# RP2350.net
KiCad netlist of a schematic drawn in Altium Designer
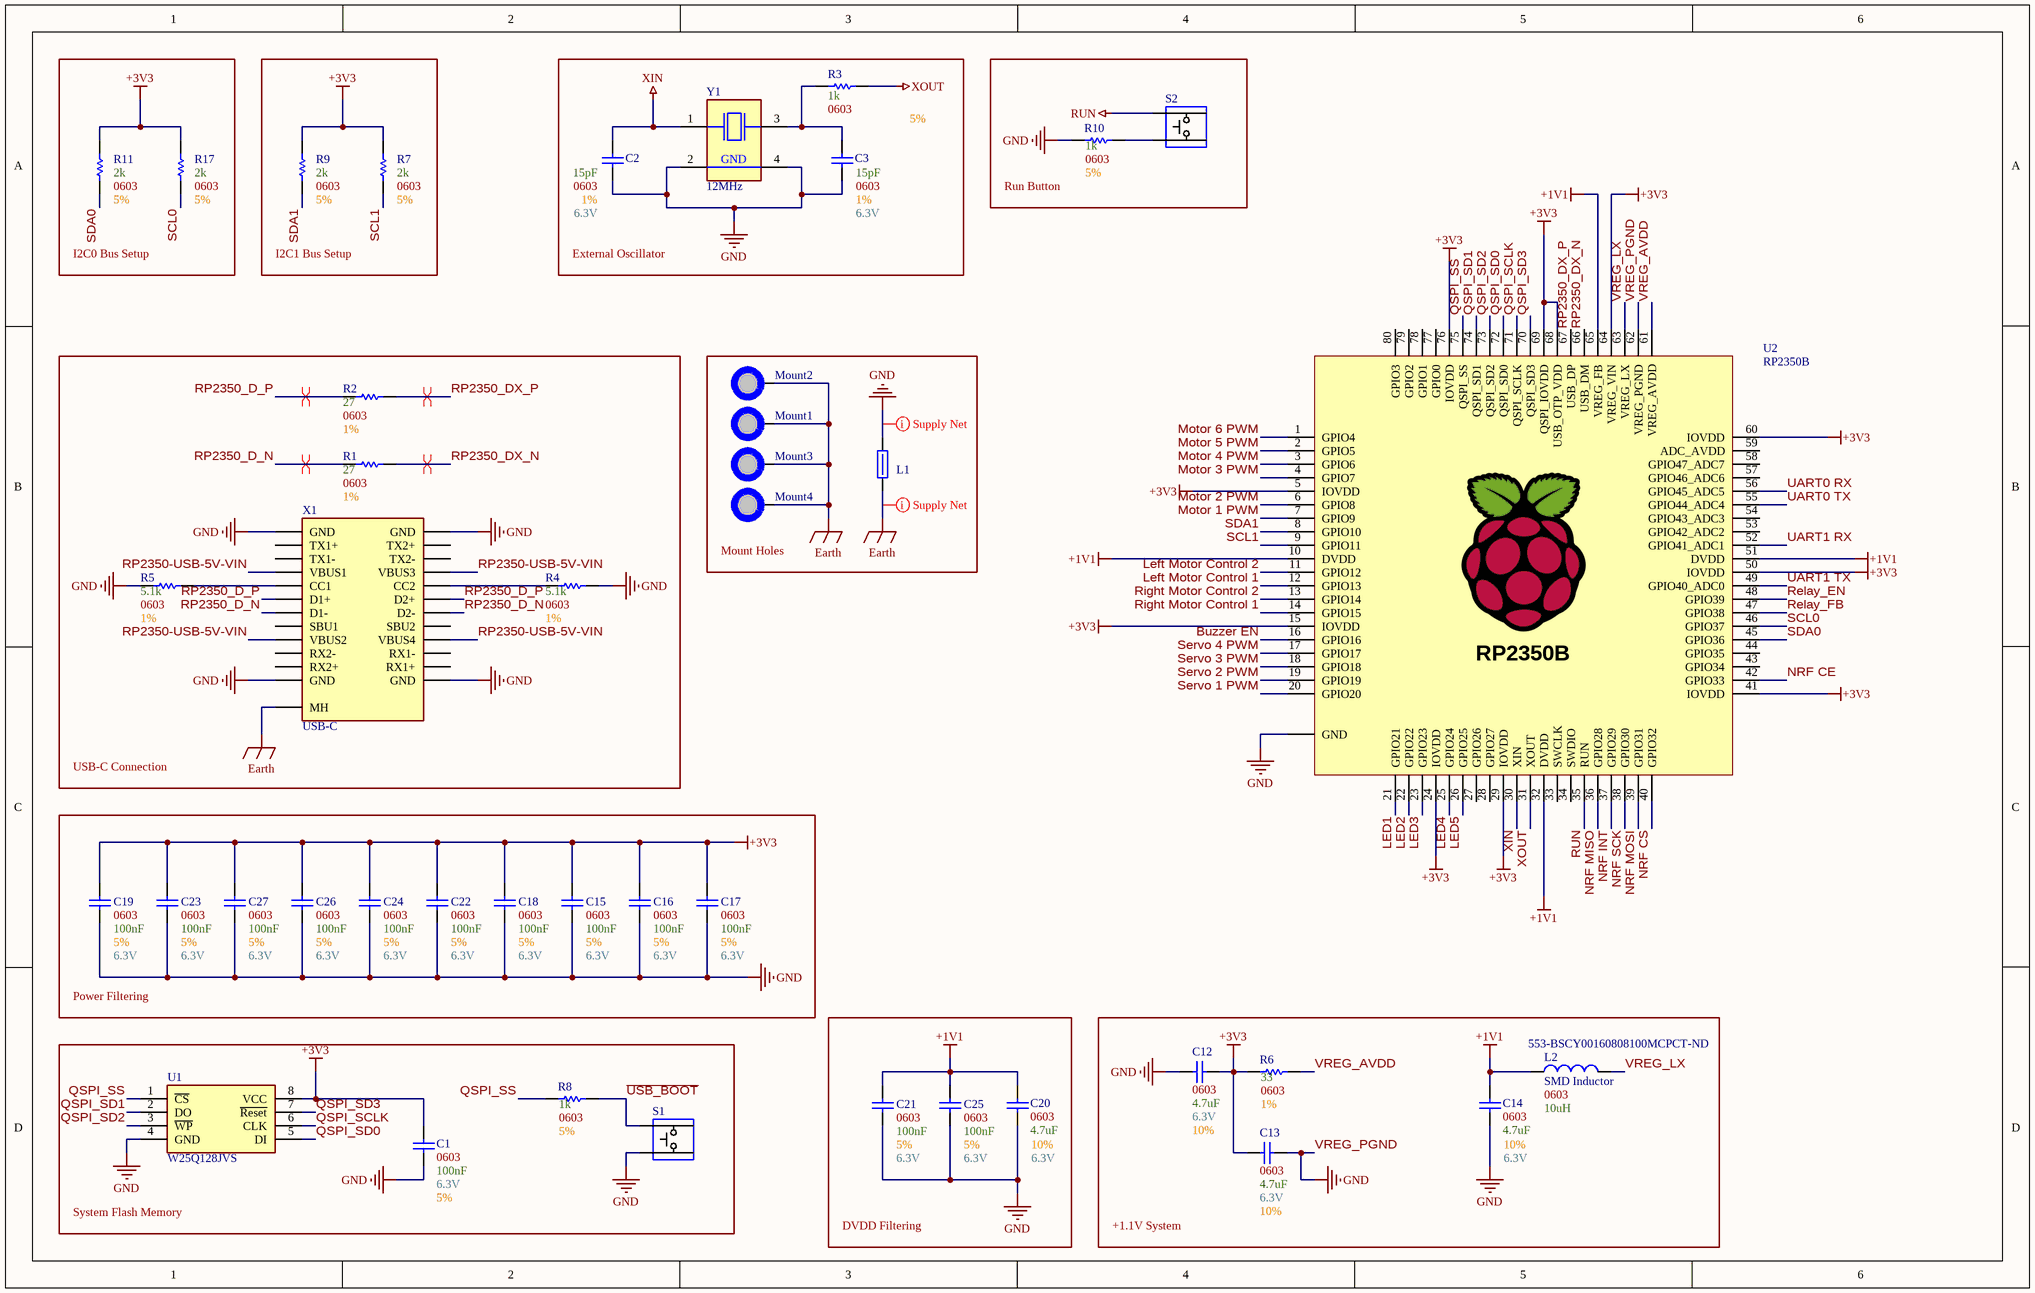
[diagram p0: RP2350.SchDoc]

(export (version "E")
  (design (tool "Eeschema 10.0.6"))
  (components
    (comp (ref "C1")
      (value "[Cap] SMD Nonpolarized")
      (footprint "[Cap] SMD 0603")
      (fields
        (field (name "SIZE PACKAGE") "0603")
        (field (name "CAPACITANCE") "100nF")
        (field (name "VOLTAGE") "6.3V")
        (field (name "TOLERANCE") "5%")
      )
      (libsource (lib "RADM Components") (part "[Cap] SMD Nonpolarized"))
    )
    (comp (ref "C2")
      (value "[Cap] SMD Nonpolarized")
      (footprint "[Cap] SMD 0603")
      (fields
        (field (name "SIZE PACKAGE") "0603")
        (field (name "CAPACITANCE") "15pF")
        (field (name "VOLTAGE") "6.3V")
        (field (name "TOLERANCE") "1%")
      )
      (libsource (lib "RADM Components") (part "[Cap] SMD Nonpolarized"))
    )
    (comp (ref "C3")
      (value "[Cap] SMD Nonpolarized")
      (footprint "[Cap] SMD 0603")
      (fields
        (field (name "SIZE PACKAGE") "0603")
        (field (name "CAPACITANCE") "15pF")
        (field (name "VOLTAGE") "6.3V")
        (field (name "TOLERANCE") "1%")
      )
      (libsource (lib "RADM Components") (part "[Cap] SMD Nonpolarized"))
    )
    (comp (ref "C12")
      (value "[Cap] SMD Nonpolarized")
      (footprint "[Cap] SMD 0603")
      (fields
        (field (name "SIZE PACKAGE") "0603")
        (field (name "CAPACITANCE") "4.7uF")
        (field (name "VOLTAGE") "6.3V")
        (field (name "TOLERANCE") "10%")
      )
      (libsource (lib "RADM Components") (part "[Cap] SMD Nonpolarized"))
    )
    (comp (ref "C13")
      (value "[Cap] SMD Nonpolarized")
      (footprint "[Cap] SMD 0603")
      (fields
        (field (name "SIZE PACKAGE") "0603")
        (field (name "CAPACITANCE") "4.7uF")
        (field (name "VOLTAGE") "6.3V")
        (field (name "TOLERANCE") "10%")
      )
      (libsource (lib "RADM Components") (part "[Cap] SMD Nonpolarized"))
    )
    (comp (ref "C14")
      (value "[Cap] SMD Nonpolarized")
      (footprint "[Cap] SMD 0603")
      (fields
        (field (name "SIZE PACKAGE") "0603")
        (field (name "CAPACITANCE") "4.7uF")
        (field (name "VOLTAGE") "6.3V")
        (field (name "TOLERANCE") "10%")
      )
      (libsource (lib "RADM Components") (part "[Cap] SMD Nonpolarized"))
    )
    (comp (ref "C15")
      (value "[Cap] SMD Nonpolarized")
      (footprint "[Cap] SMD 0603")
      (fields
        (field (name "SIZE PACKAGE") "0603")
        (field (name "CAPACITANCE") "100nF")
        (field (name "VOLTAGE") "6.3V")
        (field (name "TOLERANCE") "5%")
      )
      (libsource (lib "RADM Components") (part "[Cap] SMD Nonpolarized"))
    )
    (comp (ref "C16")
      (value "[Cap] SMD Nonpolarized")
      (footprint "[Cap] SMD 0603")
      (fields
        (field (name "SIZE PACKAGE") "0603")
        (field (name "CAPACITANCE") "100nF")
        (field (name "VOLTAGE") "6.3V")
        (field (name "TOLERANCE") "5%")
      )
      (libsource (lib "RADM Components") (part "[Cap] SMD Nonpolarized"))
    )
    (comp (ref "C17")
      (value "[Cap] SMD Nonpolarized")
      (footprint "[Cap] SMD 0603")
      (fields
        (field (name "SIZE PACKAGE") "0603")
        (field (name "CAPACITANCE") "100nF")
        (field (name "VOLTAGE") "6.3V")
        (field (name "TOLERANCE") "5%")
      )
      (libsource (lib "RADM Components") (part "[Cap] SMD Nonpolarized"))
    )
    (comp (ref "C18")
      (value "[Cap] SMD Nonpolarized")
      (footprint "[Cap] SMD 0603")
      (fields
        (field (name "SIZE PACKAGE") "0603")
        (field (name "CAPACITANCE") "100nF")
        (field (name "VOLTAGE") "6.3V")
        (field (name "TOLERANCE") "5%")
      )
      (libsource (lib "RADM Components") (part "[Cap] SMD Nonpolarized"))
    )
    (comp (ref "C19")
      (value "[Cap] SMD Nonpolarized")
      (footprint "[Cap] SMD 0603")
      (fields
        (field (name "SIZE PACKAGE") "0603")
        (field (name "CAPACITANCE") "100nF")
        (field (name "VOLTAGE") "6.3V")
        (field (name "TOLERANCE") "5%")
      )
      (libsource (lib "RADM Components") (part "[Cap] SMD Nonpolarized"))
    )
    (comp (ref "C20")
      (value "[Cap] SMD Nonpolarized")
      (footprint "[Cap] SMD 0603")
      (fields
        (field (name "SIZE PACKAGE") "0603")
        (field (name "CAPACITANCE") "4.7uF")
        (field (name "VOLTAGE") "6.3V")
        (field (name "TOLERANCE") "10%")
      )
      (libsource (lib "RADM Components") (part "[Cap] SMD Nonpolarized"))
    )
    (comp (ref "C21")
      (value "[Cap] SMD Nonpolarized")
      (footprint "[Cap] SMD 0603")
      (fields
        (field (name "SIZE PACKAGE") "0603")
        (field (name "CAPACITANCE") "100nF")
        (field (name "VOLTAGE") "6.3V")
        (field (name "TOLERANCE") "5%")
      )
      (libsource (lib "RADM Components") (part "[Cap] SMD Nonpolarized"))
    )
    (comp (ref "C22")
      (value "[Cap] SMD Nonpolarized")
      (footprint "[Cap] SMD 0603")
      (fields
        (field (name "SIZE PACKAGE") "0603")
        (field (name "CAPACITANCE") "100nF")
        (field (name "VOLTAGE") "6.3V")
        (field (name "TOLERANCE") "5%")
      )
      (libsource (lib "RADM Components") (part "[Cap] SMD Nonpolarized"))
    )
    (comp (ref "C23")
      (value "[Cap] SMD Nonpolarized")
      (footprint "[Cap] SMD 0603")
      (fields
        (field (name "SIZE PACKAGE") "0603")
        (field (name "CAPACITANCE") "100nF")
        (field (name "VOLTAGE") "6.3V")
        (field (name "TOLERANCE") "5%")
      )
      (libsource (lib "RADM Components") (part "[Cap] SMD Nonpolarized"))
    )
    (comp (ref "C24")
      (value "[Cap] SMD Nonpolarized")
      (footprint "[Cap] SMD 0603")
      (fields
        (field (name "SIZE PACKAGE") "0603")
        (field (name "CAPACITANCE") "100nF")
        (field (name "VOLTAGE") "6.3V")
        (field (name "TOLERANCE") "5%")
      )
      (libsource (lib "RADM Components") (part "[Cap] SMD Nonpolarized"))
    )
    (comp (ref "C25")
      (value "[Cap] SMD Nonpolarized")
      (footprint "[Cap] SMD 0603")
      (fields
        (field (name "SIZE PACKAGE") "0603")
        (field (name "CAPACITANCE") "100nF")
        (field (name "VOLTAGE") "6.3V")
        (field (name "TOLERANCE") "5%")
      )
      (libsource (lib "RADM Components") (part "[Cap] SMD Nonpolarized"))
    )
    (comp (ref "C26")
      (value "[Cap] SMD Nonpolarized")
      (footprint "[Cap] SMD 0603")
      (fields
        (field (name "SIZE PACKAGE") "0603")
        (field (name "CAPACITANCE") "100nF")
        (field (name "VOLTAGE") "6.3V")
        (field (name "TOLERANCE") "5%")
      )
      (libsource (lib "RADM Components") (part "[Cap] SMD Nonpolarized"))
    )
    (comp (ref "C27")
      (value "[Cap] SMD Nonpolarized")
      (footprint "[Cap] SMD 0603")
      (fields
        (field (name "SIZE PACKAGE") "0603")
        (field (name "CAPACITANCE") "100nF")
        (field (name "VOLTAGE") "6.3V")
        (field (name "TOLERANCE") "5%")
      )
      (libsource (lib "RADM Components") (part "[Cap] SMD Nonpolarized"))
    )
    (comp (ref "L1")
      (value "652-MH2029-300Y")
      (footprint "[Ferrite] SMD Bead 0805 (1)")
      (libsource (lib "RADM Components") (part "[Ferrite] SMD Ferrite Bead (1)"))
    )
    (comp (ref "L2")
      (value "SMD Inductor")
      (footprint "[Inductor] SMD 0603")
      (fields
        (field (name "SIZE PACKAGE") "0603")
        (field (name "INDUCTANCE") "10uH")
        (field (name "SUPPLIER PART NUMBER 1") "553-BSCY00160808100MCPCT-ND")
      )
      (libsource (lib "RADM Components") (part "[Inductor] SMD Inductor"))
    )
    (comp (ref "Mount1")
      (value "M3 Mount Hole")
      (footprint "[Mount] M3 Mount Hole")
      (description "Place at least 4.5mm from board edge. Plated.")
      (libsource (lib "RADM Connectors") (part "[Mount] M3 Mount Hole"))
    )
    (comp (ref "Mount2")
      (value "M3 Mount Hole")
      (footprint "[Mount] M3 Mount Hole")
      (description "Place at least 4.5mm from board edge. Plated.")
      (libsource (lib "RADM Connectors") (part "[Mount] M3 Mount Hole"))
    )
    (comp (ref "Mount3")
      (value "M3 Mount Hole")
      (footprint "[Mount] M3 Mount Hole")
      (description "Place at least 4.5mm from board edge. Plated.")
      (libsource (lib "RADM Connectors") (part "[Mount] M3 Mount Hole"))
    )
    (comp (ref "Mount4")
      (value "M3 Mount Hole")
      (footprint "[Mount] M3 Mount Hole")
      (description "Place at least 4.5mm from board edge. Plated.")
      (libsource (lib "RADM Connectors") (part "[Mount] M3 Mount Hole"))
    )
    (comp (ref "R1")
      (value "[Res] SMD Resistor")
      (footprint "[Res] SMD 0603")
      (description "Generic")
      (fields
        (field (name "TOLERANCE") "1%")
        (field (name "RESISTANCE") "27")
        (field (name "SIZE PACKAGE") "0603")
      )
      (libsource (lib "RADM Components") (part "[Res] SMD Resistor"))
    )
    (comp (ref "R2")
      (value "[Res] SMD Resistor")
      (footprint "[Res] SMD 0603")
      (description "Generic")
      (fields
        (field (name "TOLERANCE") "1%")
        (field (name "RESISTANCE") "27")
        (field (name "SIZE PACKAGE") "0603")
      )
      (libsource (lib "RADM Components") (part "[Res] SMD Resistor"))
    )
    (comp (ref "R3")
      (value "[Res] SMD Resistor")
      (footprint "[Res] SMD 0603")
      (description "Generic")
      (fields
        (field (name "RESISTANCE") "1k")
        (field (name "SIZE PACKAGE") "0603")
        (field (name "TOLERANCE") "5%")
      )
      (libsource (lib "RADM Components") (part "[Res] SMD Resistor"))
    )
    (comp (ref "R4")
      (value "[Res] SMD Resistor")
      (footprint "[Res] SMD 0603")
      (description "Generic")
      (fields
        (field (name "TOLERANCE") "1%")
        (field (name "RESISTANCE") "5.1k")
        (field (name "SIZE PACKAGE") "0603")
      )
      (libsource (lib "RADM Components") (part "[Res] SMD Resistor"))
    )
    (comp (ref "R5")
      (value "[Res] SMD Resistor")
      (footprint "[Res] SMD 0603")
      (description "Generic")
      (fields
        (field (name "TOLERANCE") "1%")
        (field (name "RESISTANCE") "5.1k")
        (field (name "SIZE PACKAGE") "0603")
      )
      (libsource (lib "RADM Components") (part "[Res] SMD Resistor"))
    )
    (comp (ref "R6")
      (value "[Res] SMD Resistor")
      (footprint "[Res] SMD 0603")
      (description "Generic")
      (fields
        (field (name "RESISTANCE") "33")
        (field (name "SIZE PACKAGE") "0603")
        (field (name "TOLERANCE") "1%")
      )
      (libsource (lib "RADM Components") (part "[Res] SMD Resistor"))
    )
    (comp (ref "R7")
      (value "[Res] SMD Resistor")
      (footprint "[Res] SMD 0603")
      (description "Generic")
      (fields
        (field (name "RESISTANCE") "2k")
        (field (name "SIZE PACKAGE") "0603")
        (field (name "TOLERANCE") "5%")
      )
      (libsource (lib "RADM Components") (part "[Res] SMD Resistor"))
    )
    (comp (ref "R8")
      (value "[Res] SMD Resistor")
      (footprint "[Res] SMD 0603")
      (description "Generic")
      (fields
        (field (name "RESISTANCE") "1k")
        (field (name "SIZE PACKAGE") "0603")
        (field (name "TOLERANCE") "5%")
      )
      (libsource (lib "RADM Components") (part "[Res] SMD Resistor"))
    )
    (comp (ref "R9")
      (value "[Res] SMD Resistor")
      (footprint "[Res] SMD 0603")
      (description "Generic")
      (fields
        (field (name "RESISTANCE") "2k")
        (field (name "SIZE PACKAGE") "0603")
        (field (name "TOLERANCE") "5%")
      )
      (libsource (lib "RADM Components") (part "[Res] SMD Resistor"))
    )
    (comp (ref "R10")
      (value "[Res] SMD Resistor")
      (footprint "[Res] SMD 0603")
      (description "Generic")
      (fields
        (field (name "RESISTANCE") "1k")
        (field (name "SIZE PACKAGE") "0603")
        (field (name "TOLERANCE") "5%")
      )
      (libsource (lib "RADM Components") (part "[Res] SMD Resistor"))
    )
    (comp (ref "R11")
      (value "[Res] SMD Resistor")
      (footprint "[Res] SMD 0603")
      (description "Generic")
      (fields
        (field (name "RESISTANCE") "2k")
        (field (name "SIZE PACKAGE") "0603")
        (field (name "TOLERANCE") "5%")
      )
      (libsource (lib "RADM Components") (part "[Res] SMD Resistor"))
    )
    (comp (ref "R17")
      (value "[Res] SMD Resistor")
      (footprint "[Res] SMD 0603")
      (description "Generic")
      (fields
        (field (name "RESISTANCE") "2k")
        (field (name "SIZE PACKAGE") "0603")
        (field (name "TOLERANCE") "5%")
      )
      (libsource (lib "RADM Components") (part "[Res] SMD Resistor"))
    )
    (comp (ref "S1")
      (value "Standard pushbutton")
      (footprint "[Switch] Pushbutton")
      (libsource (lib "RADM Components") (part "[Switch] Pushbutton"))
    )
    (comp (ref "S2")
      (value "Standard pushbutton")
      (footprint "[Switch] Pushbutton")
      (libsource (lib "RADM Components") (part "[Switch] Pushbutton"))
    )
    (comp (ref "U1")
      (value "W25Q128JVS")
      (footprint "[Mem] 16Mb Flash Memory")
      (description "W25Q128JVSIQ TR")
      (libsource (lib "RADM Components") (part "[Mem] 16Mb Flash Memory"))
    )
    (comp (ref "U2")
      (value "RP2350B")
      (footprint "[MCU] RP2350B")
      (description "QFN-80 Package")
      (libsource (lib "RADM Components") (part "[MCU] RP2350B"))
    )
    (comp (ref "X1")
      (value "USB-C")
      (footprint "[Port] USB-C")
      (libsource (lib "RADM Connectors") (part "[Port] USB Type-C"))
    )
    (comp (ref "Y1")
      (value "12MHz")
      (footprint "[XTAL] SMD 12MHz")
      (description "815-ABM8-272-T3")
      (libsource (lib "RADM Components") (part "[XTAL] SMD 12MHz"))
    )
  )
  (nets
    (net (code "1") (name "+1V1") (class "Default")
      (node (ref "C14") (pin "2") (pinfunction "2_2") (pintype "passive"))
      (node (ref "C20") (pin "2") (pinfunction "2_2") (pintype "passive"))
      (node (ref "C21") (pin "2") (pinfunction "2_2") (pintype "passive"))
      (node (ref "C25") (pin "2") (pinfunction "2_2") (pintype "passive"))
      (node (ref "L2") (pin "1") (pinfunction "1_1") (pintype "passive"))
      (node (ref "U2") (pin "10") (pinfunction "DVDD_10") (pintype "passive"))
      (node (ref "U2") (pin "32") (pinfunction "DVDD_32") (pintype "passive"))
      (node (ref "U2") (pin "51") (pinfunction "DVDD_51") (pintype "passive"))
      (node (ref "U2") (pin "65") (pinfunction "VREG_FB_65") (pintype "passive"))
    )
    (net (code "2") (name "+3V3") (class "Default")
      (node (ref "C1") (pin "1") (pinfunction "1_1") (pintype "passive"))
      (node (ref "C12") (pin "1") (pinfunction "1_1") (pintype "passive"))
      (node (ref "C13") (pin "2") (pinfunction "2_2") (pintype "passive"))
      (node (ref "C15") (pin "2") (pinfunction "2_2") (pintype "passive"))
      (node (ref "C16") (pin "2") (pinfunction "2_2") (pintype "passive"))
      (node (ref "C17") (pin "2") (pinfunction "2_2") (pintype "passive"))
      (node (ref "C18") (pin "2") (pinfunction "2_2") (pintype "passive"))
      (node (ref "C19") (pin "2") (pinfunction "2_2") (pintype "passive"))
      (node (ref "C22") (pin "2") (pinfunction "2_2") (pintype "passive"))
      (node (ref "C23") (pin "2") (pinfunction "2_2") (pintype "passive"))
      (node (ref "C24") (pin "2") (pinfunction "2_2") (pintype "passive"))
      (node (ref "C26") (pin "2") (pinfunction "2_2") (pintype "passive"))
      (node (ref "C27") (pin "2") (pinfunction "2_2") (pintype "passive"))
      (node (ref "R11") (pin "2") (pinfunction "2_2") (pintype "passive"))
      (node (ref "R17") (pin "2") (pinfunction "2_2") (pintype "passive"))
      (node (ref "R6") (pin "2") (pinfunction "2_2") (pintype "passive"))
      (node (ref "R7") (pin "2") (pinfunction "2_2") (pintype "passive"))
      (node (ref "R9") (pin "2") (pinfunction "2_2") (pintype "passive"))
      (node (ref "U1") (pin "8") (pinfunction "VCC_8") (pintype "passive"))
      (node (ref "U2") (pin "15") (pinfunction "IOVDD_15") (pintype "passive"))
      (node (ref "U2") (pin "24") (pinfunction "IOVDD_24") (pintype "passive"))
      (node (ref "U2") (pin "29") (pinfunction "IOVDD_29") (pintype "passive"))
      (node (ref "U2") (pin "41") (pinfunction "IOVDD_41") (pintype "passive"))
      (node (ref "U2") (pin "5") (pinfunction "IOVDD_5") (pintype "passive"))
      (node (ref "U2") (pin "50") (pinfunction "IOVDD_50") (pintype "passive"))
      (node (ref "U2") (pin "60") (pinfunction "IOVDD_60") (pintype "passive"))
      (node (ref "U2") (pin "64") (pinfunction "VREG_VIN_64") (pintype "passive"))
      (node (ref "U2") (pin "68") (pinfunction "USB_OTP_VDD_68") (pintype "passive"))
      (node (ref "U2") (pin "69") (pinfunction "QSPI_IOVDD_69") (pintype "passive"))
      (node (ref "U2") (pin "76") (pinfunction "IOVDD_76") (pintype "passive"))
    )
    (net (code "3") (name "/Buzzer EN") (class "Default")
      (node (ref "U2") (pin "16") (pinfunction "GPIO16_16") (pintype "passive"))
    )
    (net (code "4") (name "/LED1") (class "Default")
      (node (ref "U2") (pin "21") (pinfunction "GPIO21_21") (pintype "passive"))
    )
    (net (code "5") (name "/LED2") (class "Default")
      (node (ref "U2") (pin "22") (pinfunction "GPIO22_22") (pintype "passive"))
    )
    (net (code "6") (name "/LED3") (class "Default")
      (node (ref "U2") (pin "23") (pinfunction "GPIO23_23") (pintype "passive"))
    )
    (net (code "7") (name "/LED4") (class "Default")
      (node (ref "U2") (pin "25") (pinfunction "GPIO24_25") (pintype "passive"))
    )
    (net (code "8") (name "/LED5") (class "Default")
      (node (ref "U2") (pin "26") (pinfunction "GPIO25_26") (pintype "passive"))
    )
    (net (code "9") (name "/Left Motor Control 1") (class "Default")
      (node (ref "U2") (pin "12") (pinfunction "GPIO13_12") (pintype "passive"))
    )
    (net (code "10") (name "/Left Motor Control 2") (class "Default")
      (node (ref "U2") (pin "11") (pinfunction "GPIO12_11") (pintype "passive"))
    )
    (net (code "11") (name "/Motor 1 PWM") (class "Default")
      (node (ref "U2") (pin "7") (pinfunction "GPIO9_7") (pintype "passive"))
    )
    (net (code "12") (name "/Motor 2 PWM") (class "Default")
      (node (ref "U2") (pin "6") (pinfunction "GPIO8_6") (pintype "passive"))
    )
    (net (code "13") (name "/Motor 3 PWM") (class "Default")
      (node (ref "U2") (pin "4") (pinfunction "GPIO7_4") (pintype "passive"))
    )
    (net (code "14") (name "/Motor 4 PWM") (class "Default")
      (node (ref "U2") (pin "3") (pinfunction "GPIO6_3") (pintype "passive"))
    )
    (net (code "15") (name "/Motor 5 PWM") (class "Default")
      (node (ref "U2") (pin "2") (pinfunction "GPIO5_2") (pintype "passive"))
    )
    (net (code "16") (name "/Motor 6 PWM") (class "Default")
      (node (ref "U2") (pin "1") (pinfunction "GPIO4_1") (pintype "passive"))
    )
    (net (code "17") (name "/NRF CE") (class "Default")
      (node (ref "U2") (pin "42") (pinfunction "GPIO33_42") (pintype "passive"))
    )
    (net (code "18") (name "/NRF CS") (class "Default")
      (node (ref "U2") (pin "40") (pinfunction "GPIO32_40") (pintype "passive"))
    )
    (net (code "19") (name "/NRF INT") (class "Default")
      (node (ref "U2") (pin "37") (pinfunction "GPIO29_37") (pintype "passive"))
    )
    (net (code "20") (name "/NRF MISO") (class "Default")
      (node (ref "U2") (pin "36") (pinfunction "GPIO28_36") (pintype "passive"))
    )
    (net (code "21") (name "/NRF MOSI") (class "Default")
      (node (ref "U2") (pin "39") (pinfunction "GPIO31_39") (pintype "passive"))
    )
    (net (code "22") (name "/NRF SCK") (class "Default")
      (node (ref "U2") (pin "38") (pinfunction "GPIO30_38") (pintype "passive"))
    )
    (net (code "23") (name "/QSPI_SCLK") (class "Default")
      (node (ref "U1") (pin "6") (pinfunction "CLK_6") (pintype "passive"))
      (node (ref "U2") (pin "71") (pinfunction "QSPI_SCLK_71") (pintype "passive"))
    )
    (net (code "24") (name "/QSPI_SD0") (class "Default")
      (node (ref "U1") (pin "5") (pinfunction "DI_5") (pintype "passive"))
      (node (ref "U2") (pin "72") (pinfunction "QSPI_SD0_72") (pintype "passive"))
    )
    (net (code "25") (name "/QSPI_SD1") (class "Default")
      (node (ref "U1") (pin "2") (pinfunction "DO_2") (pintype "passive"))
      (node (ref "U2") (pin "74") (pinfunction "QSPI_SD1_74") (pintype "passive"))
    )
    (net (code "26") (name "/QSPI_SD2") (class "Default")
      (node (ref "U1") (pin "3") (pinfunction "~{WP}_3") (pintype "passive"))
      (node (ref "U2") (pin "73") (pinfunction "QSPI_SD2_73") (pintype "passive"))
    )
    (net (code "27") (name "/QSPI_SD3") (class "Default")
      (node (ref "U1") (pin "7") (pinfunction "~{Reset}_7") (pintype "passive"))
      (node (ref "U2") (pin "70") (pinfunction "QSPI_SD3_70") (pintype "passive"))
    )
    (net (code "28") (name "/QSPI_SS") (class "Default")
      (node (ref "R8") (pin "2") (pinfunction "2_2") (pintype "passive"))
      (node (ref "U1") (pin "1") (pinfunction "~{CS}_1") (pintype "passive"))
      (node (ref "U2") (pin "75") (pinfunction "QSPI_SS_75") (pintype "passive"))
    )
    (net (code "29") (name "/RP2350-USB-5V-VIN") (class "Default")
      (node (ref "X1") (pin "A4") (pinfunction "VBUS1_A4") (pintype "passive"))
      (node (ref "X1") (pin "A9") (pinfunction "VBUS2_A9") (pintype "passive"))
      (node (ref "X1") (pin "B4") (pinfunction "VBUS3_B4") (pintype "passive"))
      (node (ref "X1") (pin "B9") (pinfunction "VBUS4_B9") (pintype "passive"))
    )
    (net (code "30") (name "/RP2350_DX_N") (class "Default")
      (node (ref "R1") (pin "2") (pinfunction "2_2") (pintype "passive"))
      (node (ref "U2") (pin "66") (pinfunction "USB_DM_66") (pintype "passive"))
    )
    (net (code "31") (name "/RP2350_DX_P") (class "Default")
      (node (ref "R2") (pin "2") (pinfunction "2_2") (pintype "passive"))
      (node (ref "U2") (pin "67") (pinfunction "USB_DP_67") (pintype "passive"))
    )
    (net (code "32") (name "/RP2350_D_N") (class "Default")
      (node (ref "R1") (pin "1") (pinfunction "1_1") (pintype "passive"))
      (node (ref "X1") (pin "A7") (pinfunction "D1-_A7") (pintype "passive"))
      (node (ref "X1") (pin "B7") (pinfunction "D2-_B7") (pintype "passive"))
    )
    (net (code "33") (name "/RP2350_D_P") (class "Default")
      (node (ref "R2") (pin "1") (pinfunction "1_1") (pintype "passive"))
      (node (ref "X1") (pin "A6") (pinfunction "D1+_A6") (pintype "passive"))
      (node (ref "X1") (pin "B6") (pinfunction "D2+_B6") (pintype "passive"))
    )
    (net (code "34") (name "/Relay_EN") (class "Default")
      (node (ref "U2") (pin "48") (pinfunction "GPIO39_48") (pintype "passive"))
    )
    (net (code "35") (name "/Relay_FB") (class "Default")
      (node (ref "U2") (pin "47") (pinfunction "GPIO38_47") (pintype "passive"))
    )
    (net (code "36") (name "/Right Motor Control 1") (class "Default")
      (node (ref "U2") (pin "14") (pinfunction "GPIO15_14") (pintype "passive"))
    )
    (net (code "37") (name "/Right Motor Control 2") (class "Default")
      (node (ref "U2") (pin "13") (pinfunction "GPIO14_13") (pintype "passive"))
    )
    (net (code "38") (name "/SCL0") (class "Default")
      (node (ref "R17") (pin "1") (pinfunction "1_1") (pintype "passive"))
      (node (ref "U2") (pin "46") (pinfunction "GPIO37_46") (pintype "passive"))
    )
    (net (code "39") (name "/SCL1") (class "Default")
      (node (ref "R7") (pin "1") (pinfunction "1_1") (pintype "passive"))
      (node (ref "U2") (pin "9") (pinfunction "GPIO11_9") (pintype "passive"))
    )
    (net (code "40") (name "/SDA0") (class "Default")
      (node (ref "R11") (pin "1") (pinfunction "1_1") (pintype "passive"))
      (node (ref "U2") (pin "45") (pinfunction "GPIO36_45") (pintype "passive"))
    )
    (net (code "41") (name "/SDA1") (class "Default")
      (node (ref "R9") (pin "1") (pinfunction "1_1") (pintype "passive"))
      (node (ref "U2") (pin "8") (pinfunction "GPIO10_8") (pintype "passive"))
    )
    (net (code "42") (name "/Servo 1 PWM") (class "Default")
      (node (ref "U2") (pin "20") (pinfunction "GPIO20_20") (pintype "passive"))
    )
    (net (code "43") (name "/Servo 2 PWM") (class "Default")
      (node (ref "U2") (pin "19") (pinfunction "GPIO19_19") (pintype "passive"))
    )
    (net (code "44") (name "/Servo 3 PWM") (class "Default")
      (node (ref "U2") (pin "18") (pinfunction "GPIO18_18") (pintype "passive"))
    )
    (net (code "45") (name "/Servo 4 PWM") (class "Default")
      (node (ref "U2") (pin "17") (pinfunction "GPIO17_17") (pintype "passive"))
    )
    (net (code "46") (name "/UART0 RX") (class "Default")
      (node (ref "U2") (pin "56") (pinfunction "GPIO45_ADC5_56") (pintype "passive"))
    )
    (net (code "47") (name "/UART0 TX") (class "Default")
      (node (ref "U2") (pin "55") (pinfunction "GPIO44_ADC4_55") (pintype "passive"))
    )
    (net (code "48") (name "/UART1 RX") (class "Default")
      (node (ref "U2") (pin "52") (pinfunction "GPIO41_ADC1_52") (pintype "passive"))
    )
    (net (code "49") (name "/UART1 TX") (class "Default")
      (node (ref "U2") (pin "49") (pinfunction "GPIO40_ADC0_49") (pintype "passive"))
    )
    (net (code "50") (name "/VREG_AVDD") (class "Default")
      (node (ref "R6") (pin "1") (pinfunction "1_1") (pintype "passive"))
      (node (ref "U2") (pin "61") (pinfunction "VREG_AVDD_61") (pintype "passive"))
    )
    (net (code "51") (name "/VREG_LX") (class "Default")
      (node (ref "L2") (pin "2") (pinfunction "2_2") (pintype "passive"))
      (node (ref "U2") (pin "63") (pinfunction "VREG_LX_63") (pintype "passive"))
    )
    (net (code "52") (name "/~{USB_BOOT}") (class "Default")
      (node (ref "R8") (pin "1") (pinfunction "1_1") (pintype "passive"))
      (node (ref "S1") (pin "1") (pintype "power_in"))
    )
    (net (code "53") (name "Earth") (class "Default")
      (node (ref "L1") (pin "1") (pinfunction "1_1") (pintype "passive"))
      (node (ref "Mount1") (pin "1") (pintype "power_in"))
      (node (ref "Mount2") (pin "1") (pintype "power_in"))
      (node (ref "Mount3") (pin "1") (pintype "power_in"))
      (node (ref "Mount4") (pin "1") (pintype "power_in"))
      (node (ref "X1") (pin "MH") (pinfunction "MH_MH") (pintype "passive"))
    )
    (net (code "54") (name "GND") (class "Default")
      (node (ref "C1") (pin "2") (pinfunction "2_2") (pintype "passive"))
      (node (ref "C12") (pin "2") (pinfunction "2_2") (pintype "passive"))
      (node (ref "C13") (pin "1") (pinfunction "1_1") (pintype "passive"))
      (node (ref "C14") (pin "1") (pinfunction "1_1") (pintype "passive"))
      (node (ref "C15") (pin "1") (pinfunction "1_1") (pintype "passive"))
      (node (ref "C16") (pin "1") (pinfunction "1_1") (pintype "passive"))
      (node (ref "C17") (pin "1") (pinfunction "1_1") (pintype "passive"))
      (node (ref "C18") (pin "1") (pinfunction "1_1") (pintype "passive"))
      (node (ref "C19") (pin "1") (pinfunction "1_1") (pintype "passive"))
      (node (ref "C2") (pin "1") (pinfunction "1_1") (pintype "passive"))
      (node (ref "C20") (pin "1") (pinfunction "1_1") (pintype "passive"))
      (node (ref "C21") (pin "1") (pinfunction "1_1") (pintype "passive"))
      (node (ref "C22") (pin "1") (pinfunction "1_1") (pintype "passive"))
      (node (ref "C23") (pin "1") (pinfunction "1_1") (pintype "passive"))
      (node (ref "C24") (pin "1") (pinfunction "1_1") (pintype "passive"))
      (node (ref "C25") (pin "1") (pinfunction "1_1") (pintype "passive"))
      (node (ref "C26") (pin "1") (pinfunction "1_1") (pintype "passive"))
      (node (ref "C27") (pin "1") (pinfunction "1_1") (pintype "passive"))
      (node (ref "C3") (pin "1") (pinfunction "1_1") (pintype "passive"))
      (node (ref "L1") (pin "2") (pinfunction "2_2") (pintype "passive"))
      (node (ref "R10") (pin "2") (pinfunction "2_2") (pintype "passive"))
      (node (ref "R4") (pin "2") (pinfunction "2_2") (pintype "passive"))
      (node (ref "R5") (pin "1") (pinfunction "1_1") (pintype "passive"))
      (node (ref "S1") (pin "2") (pintype "power_in"))
      (node (ref "U1") (pin "4") (pinfunction "GND_4") (pintype "passive"))
      (node (ref "U2") (pin "62") (pinfunction "VREG_PGND_62") (pintype "passive"))
      (node (ref "U2") (pin "Pad") (pinfunction "GND_Pad") (pintype "passive"))
      (node (ref "X1") (pin "A1") (pinfunction "GND_A1") (pintype "passive"))
      (node (ref "X1") (pin "A12") (pinfunction "GND_A12") (pintype "passive"))
      (node (ref "X1") (pin "B1") (pinfunction "GND_B1") (pintype "passive"))
      (node (ref "X1") (pin "B12") (pinfunction "GND_B12") (pintype "passive"))
      (node (ref "Y1") (pin "2") (pinfunction "GND_2") (pintype "power_in"))
      (node (ref "Y1") (pin "4") (pinfunction "GND_4") (pintype "power_in"))
    )
    (net (code "55") (name "Net-(R10-Pad1)") (class "Default")
      (node (ref "R10") (pin "1") (pinfunction "1_1") (pintype "passive"))
      (node (ref "S2") (pin "2") (pintype "power_in"))
    )
    (net (code "56") (name "Net-(X1-CC1)") (class "Default")
      (node (ref "R5") (pin "2") (pinfunction "2_2") (pintype "passive"))
      (node (ref "X1") (pin "A5") (pinfunction "CC1_A5") (pintype "passive"))
    )
    (net (code "57") (name "Net-(X1-CC2)") (class "Default")
      (node (ref "R4") (pin "1") (pinfunction "1_1") (pintype "passive"))
      (node (ref "X1") (pin "B5") (pinfunction "CC2_B5") (pintype "passive"))
    )
    (net (code "58") (name "Net-(Y1-XTAL2)") (class "Default")
      (node (ref "C3") (pin "2") (pinfunction "2_2") (pintype "passive"))
      (node (ref "R3") (pin "2") (pinfunction "2_2") (pintype "passive"))
      (node (ref "Y1") (pin "3") (pinfunction "XTAL2_3") (pintype "power_in"))
    )
    (net (code "59") (name "RUN") (class "Default")
      (node (ref "S2") (pin "1") (pintype "power_in"))
      (node (ref "U2") (pin "35") (pinfunction "RUN_35") (pintype "passive"))
    )
    (net (code "60") (name "XIN") (class "Default")
      (node (ref "C2") (pin "2") (pinfunction "2_2") (pintype "passive"))
      (node (ref "U2") (pin "30") (pinfunction "XIN_30") (pintype "passive"))
      (node (ref "Y1") (pin "1") (pinfunction "XTAL1_1") (pintype "power_in"))
    )
    (net (code "61") (name "XOUT") (class "Default")
      (node (ref "R3") (pin "1") (pinfunction "1_1") (pintype "passive"))
      (node (ref "U2") (pin "31") (pinfunction "XOUT_31") (pintype "passive"))
    )
    (net (code "62") (name "unconnected-(U2-ADC_AVDD-Pad59)") (class "Default")
      (node (ref "U2") (pin "59") (pinfunction "ADC_AVDD_59") (pintype "passive"))
    )
    (net (code "63") (name "unconnected-(U2-GPIO0-Pad77)") (class "Default")
      (node (ref "U2") (pin "77") (pinfunction "GPIO0_77") (pintype "passive"))
    )
    (net (code "64") (name "unconnected-(U2-GPIO1-Pad78)") (class "Default")
      (node (ref "U2") (pin "78") (pinfunction "GPIO1_78") (pintype "passive"))
    )
    (net (code "65") (name "unconnected-(U2-GPIO2-Pad79)") (class "Default")
      (node (ref "U2") (pin "79") (pinfunction "GPIO2_79") (pintype "passive"))
    )
    (net (code "66") (name "unconnected-(U2-GPIO3-Pad80)") (class "Default")
      (node (ref "U2") (pin "80") (pinfunction "GPIO3_80") (pintype "passive"))
    )
    (net (code "67") (name "unconnected-(U2-GPIO26-Pad27)") (class "Default")
      (node (ref "U2") (pin "27") (pinfunction "GPIO26_27") (pintype "passive"))
    )
    (net (code "68") (name "unconnected-(U2-GPIO27-Pad28)") (class "Default")
      (node (ref "U2") (pin "28") (pinfunction "GPIO27_28") (pintype "passive"))
    )
    (net (code "69") (name "unconnected-(U2-GPIO34-Pad43)") (class "Default")
      (node (ref "U2") (pin "43") (pinfunction "GPIO34_43") (pintype "passive"))
    )
    (net (code "70") (name "unconnected-(U2-GPIO35-Pad44)") (class "Default")
      (node (ref "U2") (pin "44") (pinfunction "GPIO35_44") (pintype "passive"))
    )
    (net (code "71") (name "unconnected-(U2-GPIO42_ADC2-Pad53)") (class "Default")
      (node (ref "U2") (pin "53") (pinfunction "GPIO42_ADC2_53") (pintype "passive"))
    )
    (net (code "72") (name "unconnected-(U2-GPIO43_ADC3-Pad54)") (class "Default")
      (node (ref "U2") (pin "54") (pinfunction "GPIO43_ADC3_54") (pintype "passive"))
    )
    (net (code "73") (name "unconnected-(U2-GPIO46_ADC6-Pad57)") (class "Default")
      (node (ref "U2") (pin "57") (pinfunction "GPIO46_ADC6_57") (pintype "passive"))
    )
    (net (code "74") (name "unconnected-(U2-GPIO47_ADC7-Pad58)") (class "Default")
      (node (ref "U2") (pin "58") (pinfunction "GPIO47_ADC7_58") (pintype "passive"))
    )
    (net (code "75") (name "unconnected-(U2-SWCLK-Pad33)") (class "Default")
      (node (ref "U2") (pin "33") (pinfunction "SWCLK_33") (pintype "passive"))
    )
    (net (code "76") (name "unconnected-(U2-SWDIO-Pad34)") (class "Default")
      (node (ref "U2") (pin "34") (pinfunction "SWDIO_34") (pintype "passive"))
    )
    (net (code "77") (name "unconnected-(X1-RX1+-PadB11)") (class "Default")
      (node (ref "X1") (pin "B11") (pinfunction "RX1+_B11") (pintype "passive"))
    )
    (net (code "78") (name "unconnected-(X1-RX1--PadB10)") (class "Default")
      (node (ref "X1") (pin "B10") (pinfunction "RX1-_B10") (pintype "passive"))
    )
    (net (code "79") (name "unconnected-(X1-RX2+-PadA11)") (class "Default")
      (node (ref "X1") (pin "A11") (pinfunction "RX2+_A11") (pintype "passive"))
    )
    (net (code "80") (name "unconnected-(X1-RX2--PadA10)") (class "Default")
      (node (ref "X1") (pin "A10") (pinfunction "RX2-_A10") (pintype "passive"))
    )
    (net (code "81") (name "unconnected-(X1-SBU1-PadA8)") (class "Default")
      (node (ref "X1") (pin "A8") (pinfunction "SBU1_A8") (pintype "passive"))
    )
    (net (code "82") (name "unconnected-(X1-SBU2-PadB8)") (class "Default")
      (node (ref "X1") (pin "B8") (pinfunction "SBU2_B8") (pintype "passive"))
    )
    (net (code "83") (name "unconnected-(X1-TX1+-PadA2)") (class "Default")
      (node (ref "X1") (pin "A2") (pinfunction "TX1+_A2") (pintype "passive"))
    )
    (net (code "84") (name "unconnected-(X1-TX1--PadA3)") (class "Default")
      (node (ref "X1") (pin "A3") (pinfunction "TX1-_A3") (pintype "passive"))
    )
    (net (code "85") (name "unconnected-(X1-TX2+-PadB2)") (class "Default")
      (node (ref "X1") (pin "B2") (pinfunction "TX2+_B2") (pintype "passive"))
    )
    (net (code "86") (name "unconnected-(X1-TX2--PadB3)") (class "Default")
      (node (ref "X1") (pin "B3") (pinfunction "TX2-_B3") (pintype "passive"))
    )
  )
)
